# ArduiLED.net
KiCad netlist of a schematic drawn in EAGLE
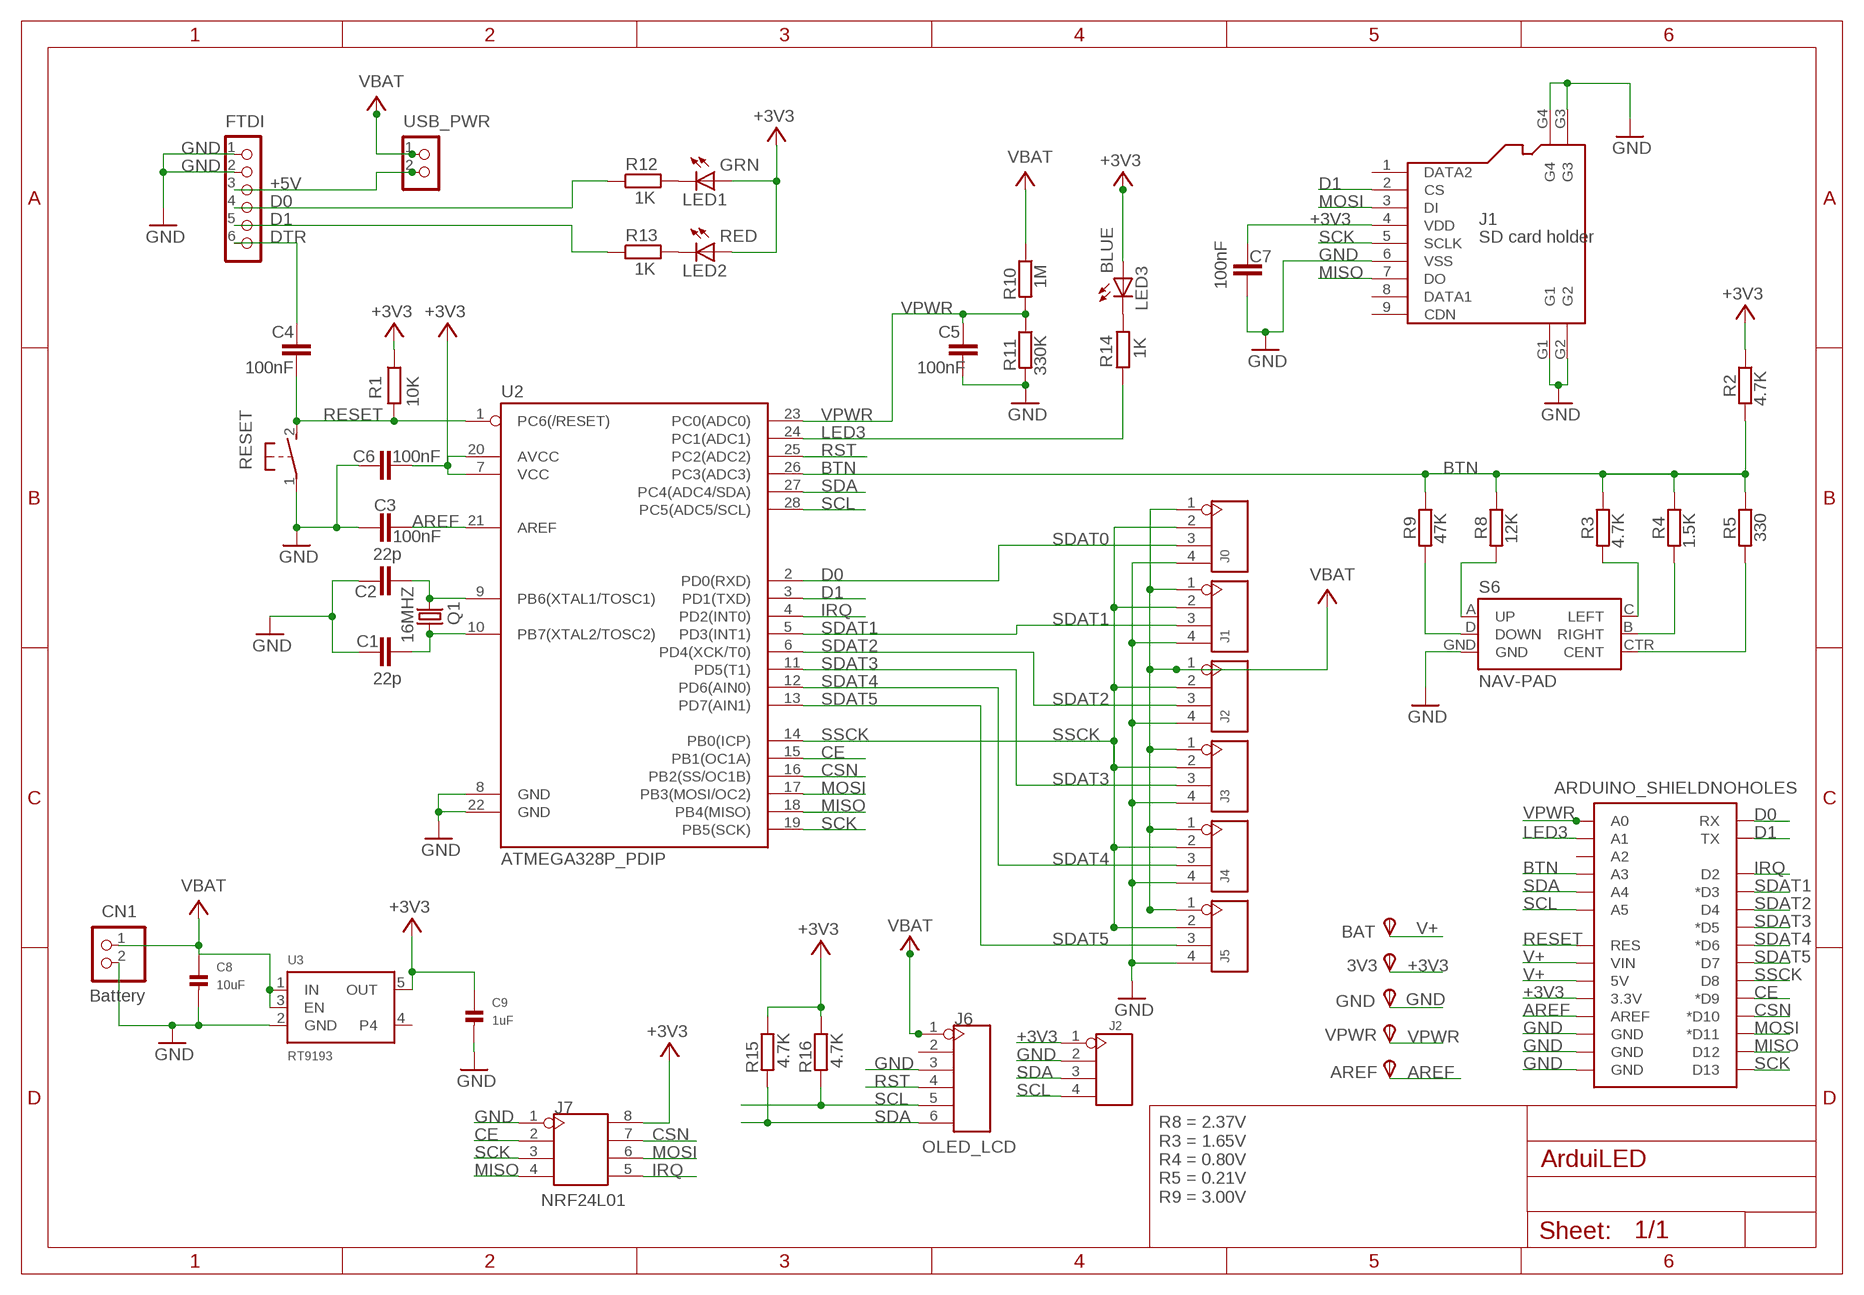
[diagram p0: schematic, sheet 1]

(export (version "E")
  (design (tool "Eeschema 10.0.6"))
  (components
    (comp (ref "3V3")
      (value "TPSPAD1-13")
      (footprint "eagle-import:P1-13")
      (libsource (lib "eagle-import") (part "TPSPAD1-13"))
    )
    (comp (ref "AREF")
      (value "TPSPAD1-13")
      (footprint "eagle-import:P1-13")
      (libsource (lib "eagle-import") (part "TPSPAD1-13"))
    )
    (comp (ref "BAT")
      (value "TPSPAD1-13")
      (footprint "eagle-import:P1-13")
      (libsource (lib "eagle-import") (part "TPSPAD1-13"))
    )
    (comp (ref "BRA")
      (value "J2")
      (footprint "eagle-import:4P-2.54-80_40MIL")
      (libsource (lib "eagle-import") (part "HEADER-4P-80/40MIL"))
    )
    (comp (ref "BRAS")
      (value "J3")
      (footprint "eagle-import:4P-2.54-80_40MIL")
      (libsource (lib "eagle-import") (part "HEADER-4P-80/40MIL"))
    )
    (comp (ref "C1")
      (value "22p")
      (footprint "eagle-import:C0805K")
      (libsource (lib "eagle-import") (part "C-EUC0805K"))
    )
    (comp (ref "C2")
      (value "22p")
      (footprint "eagle-import:C0805K")
      (libsource (lib "eagle-import") (part "C-EUC0805K"))
    )
    (comp (ref "C3")
      (value "100nF")
      (footprint "eagle-import:C0805K")
      (libsource (lib "eagle-import") (part "C-EUC0805K"))
    )
    (comp (ref "C4")
      (value "100nF")
      (footprint "eagle-import:C0805")
      (libsource (lib "eagle-import") (part "C-EUC0805"))
    )
    (comp (ref "C5")
      (value "100nF")
      (footprint "eagle-import:C0805K")
      (libsource (lib "eagle-import") (part "C-EUC0805K"))
    )
    (comp (ref "C6")
      (value "100nF")
      (footprint "eagle-import:C0805K")
      (libsource (lib "eagle-import") (part "C-EUC0805K"))
    )
    (comp (ref "C7")
      (value "100nF")
      (footprint "eagle-import:C0805K")
      (libsource (lib "eagle-import") (part "C-EUC0805K"))
    )
    (comp (ref "C8")
      (value "10uF")
      (footprint "eagle-import:0805")
      (libsource (lib "eagle-import") (part "CAP_CERAMIC0805"))
    )
    (comp (ref "C9")
      (value "1uF")
      (footprint "eagle-import:0805")
      (libsource (lib "eagle-import") (part "CAP_CERAMIC0805"))
    )
    (comp (ref "CN1")
      (value "Battery")
      (footprint "eagle-import:JST-PH-2-SMT-RA")
      (libsource (lib "eagle-import") (part "JST_2PIN-SMT-RA"))
    )
    (comp (ref "D7")
      (value "J5")
      (footprint "eagle-import:4P-2.54-80_40MIL")
      (libsource (lib "eagle-import") (part "HEADER-4P-80/40MIL"))
    )
    (comp (ref "FTDI")
      (value "CON_HEADER_1X06-PTH-RIGHT-ANGLED")
      (footprint "eagle-import:M1X6_MALE_RIGHT_ANGLED")
      (libsource (lib "eagle-import") (part "CON_HEADER_1X06-PTH-RIGHT-ANGLED"))
    )
    (comp (ref "GND")
      (value "TPSPAD1-13")
      (footprint "eagle-import:P1-13")
      (libsource (lib "eagle-import") (part "TPSPAD1-13"))
    )
    (comp (ref "J1")
      (value "SD card holder")
      (footprint "eagle-import:9P-SMD-W_-RING")
      (libsource (lib "eagle-import") (part "HOLDER-MICROSD-9P"))
    )
    (comp (ref "J2")
      (value "HEADER-4P-65/35MIL")
      (footprint "eagle-import:4P-65_35MIL")
      (libsource (lib "eagle-import") (part "HEADER-4P-65/35MIL"))
    )
    (comp (ref "J6")
      (value "OLED_LCD")
      (footprint "eagle-import:6P-2.54-65_35MIL")
      (libsource (lib "eagle-import") (part "HEADER-6P-65/35MIL"))
    )
    (comp (ref "J7")
      (value "NRF24L01")
      (footprint "eagle-import:2X4P-2.54")
      (libsource (lib "eagle-import") (part "HEADER-2X4P-2.54"))
    )
    (comp (ref "JAMB")
      (value "J4")
      (footprint "eagle-import:4P-2.54-80_40MIL")
      (libsource (lib "eagle-import") (part "HEADER-4P-80/40MIL"))
    )
    (comp (ref "LED1")
      (value "GRN")
      (footprint "eagle-import:LED-805")
      (libsource (lib "eagle-import") (part "LED-0805"))
    )
    (comp (ref "LED2")
      (value "RED")
      (footprint "eagle-import:LED-805")
      (libsource (lib "eagle-import") (part "LED-0805"))
    )
    (comp (ref "LED3")
      (value "BLUE")
      (footprint "eagle-import:LED-805")
      (libsource (lib "eagle-import") (part "LED-0805"))
    )
    (comp (ref "Q1")
      (value "16MHZ")
      (footprint "eagle-import:HC49U-V")
      (libsource (lib "eagle-import") (part "CRYSTALHC49U-V"))
    )
    (comp (ref "R1")
      (value "10K")
      (footprint "eagle-import:M0805")
      (libsource (lib "eagle-import") (part "R-EU_M0805"))
    )
    (comp (ref "R2")
      (value "4.7K")
      (footprint "eagle-import:M0805")
      (libsource (lib "eagle-import") (part "R-EU_M0805"))
    )
    (comp (ref "R3")
      (value "4.7K")
      (footprint "eagle-import:M0805")
      (libsource (lib "eagle-import") (part "R-EU_M0805"))
    )
    (comp (ref "R4")
      (value "1.5K")
      (footprint "eagle-import:M0805")
      (libsource (lib "eagle-import") (part "R-EU_M0805"))
    )
    (comp (ref "R5")
      (value "330")
      (footprint "eagle-import:M0805")
      (libsource (lib "eagle-import") (part "R-EU_M0805"))
    )
    (comp (ref "R8")
      (value "12K")
      (footprint "eagle-import:M0805")
      (libsource (lib "eagle-import") (part "R-EU_M0805"))
    )
    (comp (ref "R9")
      (value "47K")
      (footprint "eagle-import:M0805")
      (libsource (lib "eagle-import") (part "R-EU_M0805"))
    )
    (comp (ref "R10")
      (value "1M")
      (footprint "eagle-import:M0805")
      (libsource (lib "eagle-import") (part "R-EU_M0805"))
    )
    (comp (ref "R11")
      (value "330K")
      (footprint "eagle-import:M0805")
      (libsource (lib "eagle-import") (part "R-EU_M0805"))
    )
    (comp (ref "R12")
      (value "1K")
      (footprint "eagle-import:M0805")
      (libsource (lib "eagle-import") (part "R-EU_M0805"))
    )
    (comp (ref "R13")
      (value "1K")
      (footprint "eagle-import:M0805")
      (libsource (lib "eagle-import") (part "R-EU_M0805"))
    )
    (comp (ref "R14")
      (value "1K")
      (footprint "eagle-import:M0805")
      (libsource (lib "eagle-import") (part "R-EU_M0805"))
    )
    (comp (ref "R15")
      (value "4.7K")
      (footprint "eagle-import:M0805")
      (libsource (lib "eagle-import") (part "R-EU_M0805"))
    )
    (comp (ref "R16")
      (value "4.7K")
      (footprint "eagle-import:M0805")
      (libsource (lib "eagle-import") (part "R-EU_M0805"))
    )
    (comp (ref "RESET")
      (value "DTSM-3")
      (footprint "eagle-import:DTSM-3")
      (libsource (lib "eagle-import") (part "DTSM-3"))
    )
    (comp (ref "S6")
      (value "NAV-PAD")
      (footprint "eagle-import:JOYSTICK_MINI")
      (libsource (lib "eagle-import") (part "JOYSTICK_MINI"))
    )
    (comp (ref "TETE")
      (value "J0")
      (footprint "eagle-import:4P-2.54-80_40MIL")
      (libsource (lib "eagle-import") (part "HEADER-4P-80/40MIL"))
    )
    (comp (ref "TRONC")
      (value "J1")
      (footprint "eagle-import:4P-2.54-80_40MIL")
      (libsource (lib "eagle-import") (part "HEADER-4P-80/40MIL"))
    )
    (comp (ref "U1")
      (value "ARDUINO_SHIELDNOHOLES")
      (footprint "eagle-import:DUEMILANOVE_SHIELD_NOHOLES")
      (libsource (lib "eagle-import") (part "ARDUINO_SHIELDNOHOLES"))
    )
    (comp (ref "U2")
      (value "ATMEGA328P_PDIP")
      (footprint "eagle-import:DIL28-3")
      (libsource (lib "eagle-import") (part "ATMEGA328P_PDIP"))
    )
    (comp (ref "U3")
      (value "RT9193")
      (footprint "eagle-import:SOT23-5")
      (libsource (lib "eagle-import") (part "VREG_SOT23-5"))
    )
    (comp (ref "USB_PWR")
      (value "CON_HEADER_1X02-PTH")
      (footprint "eagle-import:M1X2")
      (libsource (lib "eagle-import") (part "CON_HEADER_1X02-PTH"))
    )
    (comp (ref "VPWR")
      (value "TPSPAD1-13")
      (footprint "eagle-import:P1-13")
      (libsource (lib "eagle-import") (part "TPSPAD1-13"))
    )
  )
  (nets
    (net (code "1") (name "+3V3") (class "Default")
      (node (ref "3V3") (pin "TP") (pinfunction "PP_TP") (pintype "input"))
      (node (ref "C6") (pin "2") (pinfunction "2_2") (pintype "passive"))
      (node (ref "C7") (pin "1") (pinfunction "1_1") (pintype "passive"))
      (node (ref "C9") (pin "1") (pinfunction "P$1_1") (pintype "passive"))
      (node (ref "J1") (pin "4") (pinfunction "VDD_4") (pintype "bidirectional"))
      (node (ref "J2") (pin "1") (pinfunction "P$1_1") (pintype "bidirectional"))
      (node (ref "J7") (pin "8") (pinfunction "8_8") (pintype "bidirectional"))
      (node (ref "LED1") (pin "A") (pinfunction "A_A") (pintype "passive"))
      (node (ref "LED2") (pin "A") (pinfunction "A_A") (pintype "passive"))
      (node (ref "LED3") (pin "A") (pinfunction "A_A") (pintype "passive"))
      (node (ref "R1") (pin "1") (pinfunction "1_1") (pintype "passive"))
      (node (ref "R15") (pin "1") (pinfunction "1_1") (pintype "passive"))
      (node (ref "R16") (pin "1") (pinfunction "1_1") (pintype "passive"))
      (node (ref "R2") (pin "1") (pinfunction "1_1") (pintype "passive"))
      (node (ref "U1") (pin "3.3V") (pinfunction "3.3V_3.3V") (pintype "bidirectional"))
      (node (ref "U2") (pin "20") (pinfunction "AVCC_20") (pintype "bidirectional"))
      (node (ref "U2") (pin "7") (pinfunction "VCC_7") (pintype "bidirectional"))
      (node (ref "U3") (pin "5") (pinfunction "OUT_5") (pintype "bidirectional"))
    )
    (net (code "2") (name "/+5V") (class "Default")
      (node (ref "FTDI") (pin "3") (pinfunction "3_3") (pintype "passive"))
      (node (ref "USB_PWR") (pin "2") (pinfunction "2_2") (pintype "passive"))
    )
    (net (code "3") (name "/AREF") (class "Default")
      (node (ref "AREF") (pin "TP") (pinfunction "PP_TP") (pintype "input"))
      (node (ref "C3") (pin "1") (pinfunction "1_1") (pintype "passive"))
      (node (ref "U1") (pin "AREF") (pinfunction "AREF_AREF") (pintype "bidirectional"))
      (node (ref "U2") (pin "21") (pinfunction "AREF_21") (pintype "bidirectional"))
    )
    (net (code "4") (name "/BTN") (class "Default")
      (node (ref "R2") (pin "2") (pinfunction "2_2") (pintype "passive"))
      (node (ref "R3") (pin "1") (pinfunction "1_1") (pintype "passive"))
      (node (ref "R4") (pin "1") (pinfunction "1_1") (pintype "passive"))
      (node (ref "R5") (pin "1") (pinfunction "1_1") (pintype "passive"))
      (node (ref "R8") (pin "1") (pinfunction "1_1") (pintype "passive"))
      (node (ref "R9") (pin "1") (pinfunction "1_1") (pintype "passive"))
      (node (ref "U1") (pin "A3") (pinfunction "A3_A3") (pintype "bidirectional"))
      (node (ref "U2") (pin "26") (pinfunction "PC3(ADC3)_26") (pintype "bidirectional"))
    )
    (net (code "5") (name "/CE") (class "Default")
      (node (ref "J7") (pin "2") (pinfunction "2_2") (pintype "bidirectional"))
      (node (ref "U1") (pin "D9") (pinfunction "*D9_D9") (pintype "bidirectional"))
      (node (ref "U2") (pin "15") (pinfunction "PB1(OC1A)_15") (pintype "bidirectional"))
    )
    (net (code "6") (name "/CSN") (class "Default")
      (node (ref "J7") (pin "7") (pinfunction "7_7") (pintype "bidirectional"))
      (node (ref "U1") (pin "D10") (pinfunction "*D10_D10") (pintype "bidirectional"))
      (node (ref "U2") (pin "16") (pinfunction "PB2(SS/OC1B)_16") (pintype "bidirectional"))
    )
    (net (code "7") (name "/D0") (class "Default")
      (node (ref "FTDI") (pin "4") (pinfunction "4_4") (pintype "passive"))
      (node (ref "R12") (pin "1") (pinfunction "1_1") (pintype "passive"))
      (node (ref "TETE") (pin "3") (pinfunction "P$3_3") (pintype "bidirectional"))
      (node (ref "U1") (pin "RX") (pinfunction "RX_RX") (pintype "bidirectional"))
      (node (ref "U2") (pin "2") (pinfunction "PD0(RXD)_2") (pintype "bidirectional"))
    )
    (net (code "8") (name "/D1") (class "Default")
      (node (ref "FTDI") (pin "5") (pinfunction "5_5") (pintype "passive"))
      (node (ref "J1") (pin "2") (pinfunction "CS_2") (pintype "bidirectional"))
      (node (ref "R13") (pin "1") (pinfunction "1_1") (pintype "passive"))
      (node (ref "U1") (pin "TX") (pinfunction "TX_TX") (pintype "bidirectional"))
      (node (ref "U2") (pin "3") (pinfunction "PD1(TXD)_3") (pintype "bidirectional"))
    )
    (net (code "9") (name "/DTR") (class "Default")
      (node (ref "C4") (pin "1") (pinfunction "1_1") (pintype "passive"))
      (node (ref "FTDI") (pin "6") (pinfunction "6_6") (pintype "passive"))
    )
    (net (code "10") (name "/IRQ") (class "Default")
      (node (ref "J7") (pin "5") (pinfunction "5_5") (pintype "bidirectional"))
      (node (ref "U1") (pin "D2") (pinfunction "D2_D2") (pintype "bidirectional"))
      (node (ref "U2") (pin "4") (pinfunction "PD2(INT0)_4") (pintype "bidirectional"))
    )
    (net (code "11") (name "/LED3") (class "Default")
      (node (ref "R14") (pin "1") (pinfunction "1_1") (pintype "passive"))
      (node (ref "U1") (pin "A1") (pinfunction "A1_A1") (pintype "bidirectional"))
      (node (ref "U2") (pin "24") (pinfunction "PC1(ADC1)_24") (pintype "bidirectional"))
    )
    (net (code "12") (name "/MISO") (class "Default")
      (node (ref "J1") (pin "7") (pinfunction "DO_7") (pintype "bidirectional"))
      (node (ref "J7") (pin "4") (pinfunction "4_4") (pintype "bidirectional"))
      (node (ref "U1") (pin "D12") (pinfunction "D12_D12") (pintype "bidirectional"))
      (node (ref "U2") (pin "18") (pinfunction "PB4(MISO)_18") (pintype "bidirectional"))
    )
    (net (code "13") (name "/MOSI") (class "Default")
      (node (ref "J1") (pin "3") (pinfunction "DI_3") (pintype "bidirectional"))
      (node (ref "J7") (pin "6") (pinfunction "6_6") (pintype "bidirectional"))
      (node (ref "U1") (pin "D11") (pinfunction "*D11_D11") (pintype "bidirectional"))
      (node (ref "U2") (pin "17") (pinfunction "PB3(MOSI/OC2)_17") (pintype "bidirectional"))
    )
    (net (code "14") (name "/RESET") (class "Default")
      (node (ref "C4") (pin "2") (pinfunction "2_2") (pintype "passive"))
      (node (ref "R1") (pin "2") (pinfunction "2_2") (pintype "passive"))
      (node (ref "RESET") (pin "2") (pinfunction "2_2") (pintype "passive"))
      (node (ref "U1") (pin "RES") (pinfunction "RES_RES") (pintype "bidirectional"))
      (node (ref "U2") (pin "1") (pinfunction "PC6(/RESET)_1") (pintype "bidirectional"))
    )
    (net (code "15") (name "/RST") (class "Default")
      (node (ref "J6") (pin "4") (pinfunction "4_4") (pintype "bidirectional"))
      (node (ref "U2") (pin "25") (pinfunction "PC2(ADC2)_25") (pintype "bidirectional"))
    )
    (net (code "16") (name "/SCK") (class "Default")
      (node (ref "J1") (pin "5") (pinfunction "SCLK_5") (pintype "bidirectional"))
      (node (ref "J7") (pin "3") (pinfunction "3_3") (pintype "bidirectional"))
      (node (ref "U1") (pin "D13") (pinfunction "D13_D13") (pintype "bidirectional"))
      (node (ref "U2") (pin "19") (pinfunction "PB5(SCK)_19") (pintype "bidirectional"))
    )
    (net (code "17") (name "/SCL") (class "Default")
      (node (ref "J2") (pin "4") (pinfunction "P$4_4") (pintype "bidirectional"))
      (node (ref "J6") (pin "5") (pinfunction "5_5") (pintype "bidirectional"))
      (node (ref "R16") (pin "2") (pinfunction "2_2") (pintype "passive"))
      (node (ref "U1") (pin "A5") (pinfunction "A5_A5") (pintype "bidirectional"))
      (node (ref "U2") (pin "28") (pinfunction "PC5(ADC5/SCL)_28") (pintype "bidirectional"))
    )
    (net (code "18") (name "/SDA") (class "Default")
      (node (ref "J2") (pin "3") (pinfunction "P$3_3") (pintype "bidirectional"))
      (node (ref "J6") (pin "6") (pinfunction "6_6") (pintype "bidirectional"))
      (node (ref "R15") (pin "2") (pinfunction "2_2") (pintype "passive"))
      (node (ref "U1") (pin "A4") (pinfunction "A4_A4") (pintype "bidirectional"))
      (node (ref "U2") (pin "27") (pinfunction "PC4(ADC4/SDA)_27") (pintype "bidirectional"))
    )
    (net (code "19") (name "/SDAT1") (class "Default")
      (node (ref "TRONC") (pin "3") (pinfunction "P$3_3") (pintype "bidirectional"))
      (node (ref "U1") (pin "D3") (pinfunction "*D3_D3") (pintype "bidirectional"))
      (node (ref "U2") (pin "5") (pinfunction "PD3(INT1)_5") (pintype "bidirectional"))
    )
    (net (code "20") (name "/SDAT2") (class "Default")
      (node (ref "BRA") (pin "3") (pinfunction "P$3_3") (pintype "bidirectional"))
      (node (ref "U1") (pin "D4") (pinfunction "D4_D4") (pintype "bidirectional"))
      (node (ref "U2") (pin "6") (pinfunction "PD4(XCK/T0)_6") (pintype "bidirectional"))
    )
    (net (code "21") (name "/SDAT3") (class "Default")
      (node (ref "BRAS") (pin "3") (pinfunction "P$3_3") (pintype "bidirectional"))
      (node (ref "U1") (pin "D5") (pinfunction "*D5_D5") (pintype "bidirectional"))
      (node (ref "U2") (pin "11") (pinfunction "PD5(T1)_11") (pintype "bidirectional"))
    )
    (net (code "22") (name "/SDAT4") (class "Default")
      (node (ref "JAMB") (pin "3") (pinfunction "P$3_3") (pintype "bidirectional"))
      (node (ref "U1") (pin "D6") (pinfunction "*D6_D6") (pintype "bidirectional"))
      (node (ref "U2") (pin "12") (pinfunction "PD6(AIN0)_12") (pintype "bidirectional"))
    )
    (net (code "23") (name "/SDAT5") (class "Default")
      (node (ref "D7") (pin "3") (pinfunction "P$3_3") (pintype "bidirectional"))
      (node (ref "U1") (pin "D7") (pinfunction "D7_D7") (pintype "bidirectional"))
      (node (ref "U2") (pin "13") (pinfunction "PD7(AIN1)_13") (pintype "bidirectional"))
    )
    (net (code "24") (name "/SSCK") (class "Default")
      (node (ref "BRA") (pin "2") (pinfunction "P$2_2") (pintype "bidirectional"))
      (node (ref "BRAS") (pin "2") (pinfunction "P$2_2") (pintype "bidirectional"))
      (node (ref "D7") (pin "2") (pinfunction "P$2_2") (pintype "bidirectional"))
      (node (ref "JAMB") (pin "2") (pinfunction "P$2_2") (pintype "bidirectional"))
      (node (ref "TETE") (pin "2") (pinfunction "P$2_2") (pintype "bidirectional"))
      (node (ref "TRONC") (pin "2") (pinfunction "P$2_2") (pintype "bidirectional"))
      (node (ref "U1") (pin "D8") (pinfunction "D8_D8") (pintype "bidirectional"))
      (node (ref "U2") (pin "14") (pinfunction "PB0(ICP)_14") (pintype "bidirectional"))
    )
    (net (code "25") (name "/VPWR") (class "Default")
      (node (ref "C5") (pin "1") (pinfunction "1_1") (pintype "passive"))
      (node (ref "R10") (pin "2") (pinfunction "2_2") (pintype "passive"))
      (node (ref "R11") (pin "1") (pinfunction "1_1") (pintype "passive"))
      (node (ref "U1") (pin "A0") (pinfunction "A0_A0") (pintype "bidirectional"))
      (node (ref "U2") (pin "23") (pinfunction "PC0(ADC0)_23") (pintype "bidirectional"))
      (node (ref "VPWR") (pin "TP") (pinfunction "PP_TP") (pintype "input"))
    )
    (net (code "26") (name "GND") (class "Default")
      (node (ref "BRA") (pin "4") (pinfunction "P$4_4") (pintype "bidirectional"))
      (node (ref "BRAS") (pin "4") (pinfunction "P$4_4") (pintype "bidirectional"))
      (node (ref "C1") (pin "1") (pinfunction "1_1") (pintype "passive"))
      (node (ref "C2") (pin "1") (pinfunction "1_1") (pintype "passive"))
      (node (ref "C3") (pin "2") (pinfunction "2_2") (pintype "passive"))
      (node (ref "C5") (pin "2") (pinfunction "2_2") (pintype "passive"))
      (node (ref "C6") (pin "1") (pinfunction "1_1") (pintype "passive"))
      (node (ref "C7") (pin "2") (pinfunction "2_2") (pintype "passive"))
      (node (ref "C8") (pin "2") (pinfunction "P$2_2") (pintype "passive"))
      (node (ref "C9") (pin "2") (pinfunction "P$2_2") (pintype "passive"))
      (node (ref "CN1") (pin "2") (pinfunction "1_2") (pintype "passive"))
      (node (ref "D7") (pin "4") (pinfunction "P$4_4") (pintype "bidirectional"))
      (node (ref "FTDI") (pin "1") (pinfunction "1_1") (pintype "bidirectional"))
      (node (ref "FTDI") (pin "2") (pinfunction "2_2") (pintype "bidirectional"))
      (node (ref "GND") (pin "TP") (pinfunction "PP_TP") (pintype "input"))
      (node (ref "J1") (pin "6") (pinfunction "VSS_6") (pintype "bidirectional"))
      (node (ref "J1") (pin "G1") (pinfunction "G1_G1") (pintype "bidirectional"))
      (node (ref "J1") (pin "G2") (pinfunction "G2_G2") (pintype "bidirectional"))
      (node (ref "J1") (pin "G3") (pinfunction "G3_G3") (pintype "bidirectional"))
      (node (ref "J1") (pin "G4") (pinfunction "G4_G4") (pintype "bidirectional"))
      (node (ref "J2") (pin "2") (pinfunction "P$2_2") (pintype "bidirectional"))
      (node (ref "J6") (pin "3") (pinfunction "3_3") (pintype "bidirectional"))
      (node (ref "J7") (pin "1") (pinfunction "1_1") (pintype "bidirectional"))
      (node (ref "JAMB") (pin "4") (pinfunction "P$4_4") (pintype "bidirectional"))
      (node (ref "R11") (pin "2") (pinfunction "2_2") (pintype "passive"))
      (node (ref "RESET") (pin "1") (pinfunction "1_1") (pintype "passive"))
      (node (ref "S6") (pin "GND") (pinfunction "GND_GND") (pintype "bidirectional"))
      (node (ref "TETE") (pin "4") (pinfunction "P$4_4") (pintype "bidirectional"))
      (node (ref "TRONC") (pin "4") (pinfunction "P$4_4") (pintype "bidirectional"))
      (node (ref "U1") (pin "GND@0") (pinfunction "GND_GND@0") (pintype "bidirectional"))
      (node (ref "U1") (pin "GND@1") (pinfunction "GND_GND@1") (pintype "bidirectional"))
      (node (ref "U1") (pin "GND@2") (pinfunction "GND_GND@2") (pintype "bidirectional"))
      (node (ref "U2") (pin "22") (pinfunction "GND_22") (pintype "bidirectional"))
      (node (ref "U2") (pin "8") (pinfunction "GND_8") (pintype "bidirectional"))
      (node (ref "U3") (pin "2") (pinfunction "GND_2") (pintype "bidirectional"))
    )
    (net (code "27") (name "Net-(LED1-PadC)") (class "Default")
      (node (ref "LED1") (pin "C") (pinfunction "C_C") (pintype "passive"))
      (node (ref "R12") (pin "2") (pinfunction "2_2") (pintype "passive"))
    )
    (net (code "28") (name "Net-(LED2-PadC)") (class "Default")
      (node (ref "LED2") (pin "C") (pinfunction "C_C") (pintype "passive"))
      (node (ref "R13") (pin "2") (pinfunction "2_2") (pintype "passive"))
    )
    (net (code "29") (name "Net-(LED3-PadC)") (class "Default")
      (node (ref "LED3") (pin "C") (pinfunction "C_C") (pintype "passive"))
      (node (ref "R14") (pin "2") (pinfunction "2_2") (pintype "passive"))
    )
    (net (code "30") (name "Net-(S6-CENT)") (class "Default")
      (node (ref "R5") (pin "2") (pinfunction "2_2") (pintype "passive"))
      (node (ref "S6") (pin "CTR") (pinfunction "CENT_CTR") (pintype "bidirectional"))
    )
    (net (code "31") (name "Net-(S6-DOWN)") (class "Default")
      (node (ref "R9") (pin "2") (pinfunction "2_2") (pintype "passive"))
      (node (ref "S6") (pin "D") (pinfunction "DOWN_D") (pintype "bidirectional"))
    )
    (net (code "32") (name "Net-(S6-LEFT)") (class "Default")
      (node (ref "R3") (pin "2") (pinfunction "2_2") (pintype "passive"))
      (node (ref "S6") (pin "C") (pinfunction "LEFT_C") (pintype "bidirectional"))
    )
    (net (code "33") (name "Net-(S6-RIGHT)") (class "Default")
      (node (ref "R4") (pin "2") (pinfunction "2_2") (pintype "passive"))
      (node (ref "S6") (pin "B") (pinfunction "RIGHT_B") (pintype "bidirectional"))
    )
    (net (code "34") (name "Net-(S6-UP)") (class "Default")
      (node (ref "R8") (pin "2") (pinfunction "2_2") (pintype "passive"))
      (node (ref "S6") (pin "A") (pinfunction "UP_A") (pintype "bidirectional"))
    )
    (net (code "35") (name "Net-(U2-PB6(XTAL1{slash}TOSC1))") (class "Default")
      (node (ref "C2") (pin "2") (pinfunction "2_2") (pintype "passive"))
      (node (ref "Q1") (pin "2") (pinfunction "2_2") (pintype "passive"))
      (node (ref "U2") (pin "9") (pinfunction "PB6(XTAL1/TOSC1)_9") (pintype "bidirectional"))
    )
    (net (code "36") (name "Net-(U2-PB7(XTAL2{slash}TOSC2))") (class "Default")
      (node (ref "C1") (pin "2") (pinfunction "2_2") (pintype "passive"))
      (node (ref "Q1") (pin "1") (pinfunction "1_1") (pintype "passive"))
      (node (ref "U2") (pin "10") (pinfunction "PB7(XTAL2/TOSC2)_10") (pintype "bidirectional"))
    )
    (net (code "37") (name "VBAT") (class "Default")
      (node (ref "BAT") (pin "TP") (pinfunction "PP_TP") (pintype "input"))
      (node (ref "BRA") (pin "1") (pinfunction "P$1_1") (pintype "bidirectional"))
      (node (ref "BRAS") (pin "1") (pinfunction "P$1_1") (pintype "bidirectional"))
      (node (ref "C8") (pin "1") (pinfunction "P$1_1") (pintype "passive"))
      (node (ref "CN1") (pin "1") (pinfunction "2_1") (pintype "passive"))
      (node (ref "D7") (pin "1") (pinfunction "P$1_1") (pintype "bidirectional"))
      (node (ref "J6") (pin "1") (pinfunction "1_1") (pintype "bidirectional"))
      (node (ref "JAMB") (pin "1") (pinfunction "P$1_1") (pintype "bidirectional"))
      (node (ref "R10") (pin "1") (pinfunction "1_1") (pintype "passive"))
      (node (ref "TETE") (pin "1") (pinfunction "P$1_1") (pintype "bidirectional"))
      (node (ref "TRONC") (pin "1") (pinfunction "P$1_1") (pintype "bidirectional"))
      (node (ref "U1") (pin "5V") (pinfunction "5V_5V") (pintype "bidirectional"))
      (node (ref "U1") (pin "VIN") (pinfunction "VIN_VIN") (pintype "bidirectional"))
      (node (ref "U3") (pin "1") (pinfunction "IN_1") (pintype "bidirectional"))
      (node (ref "U3") (pin "3") (pinfunction "EN_3") (pintype "bidirectional"))
      (node (ref "USB_PWR") (pin "1") (pinfunction "1_1") (pintype "passive"))
    )
    (net (code "38") (name "unconnected-(J1-CDN-Pad9)") (class "Default")
      (node (ref "J1") (pin "9") (pinfunction "CDN_9") (pintype "bidirectional"))
    )
    (net (code "39") (name "unconnected-(J1-DATA1-Pad8)") (class "Default")
      (node (ref "J1") (pin "8") (pinfunction "DATA1_8") (pintype "bidirectional"))
    )
    (net (code "40") (name "unconnected-(J1-DATA2-Pad1)") (class "Default")
      (node (ref "J1") (pin "1") (pinfunction "DATA2_1") (pintype "bidirectional"))
    )
    (net (code "41") (name "unconnected-(J6-Pad2)") (class "Default")
      (node (ref "J6") (pin "2") (pinfunction "2_2") (pintype "bidirectional"))
    )
    (net (code "42") (name "unconnected-(U1-PadA2)") (class "Default")
      (node (ref "U1") (pin "A2") (pinfunction "A2_A2") (pintype "bidirectional"))
    )
    (net (code "43") (name "unconnected-(U3-P4-Pad4)") (class "Default")
      (node (ref "U3") (pin "4") (pinfunction "P4_4") (pintype "bidirectional"))
    )
  )
)
